# connectors.net
KiCad netlist of a schematic drawn in Altium Designer
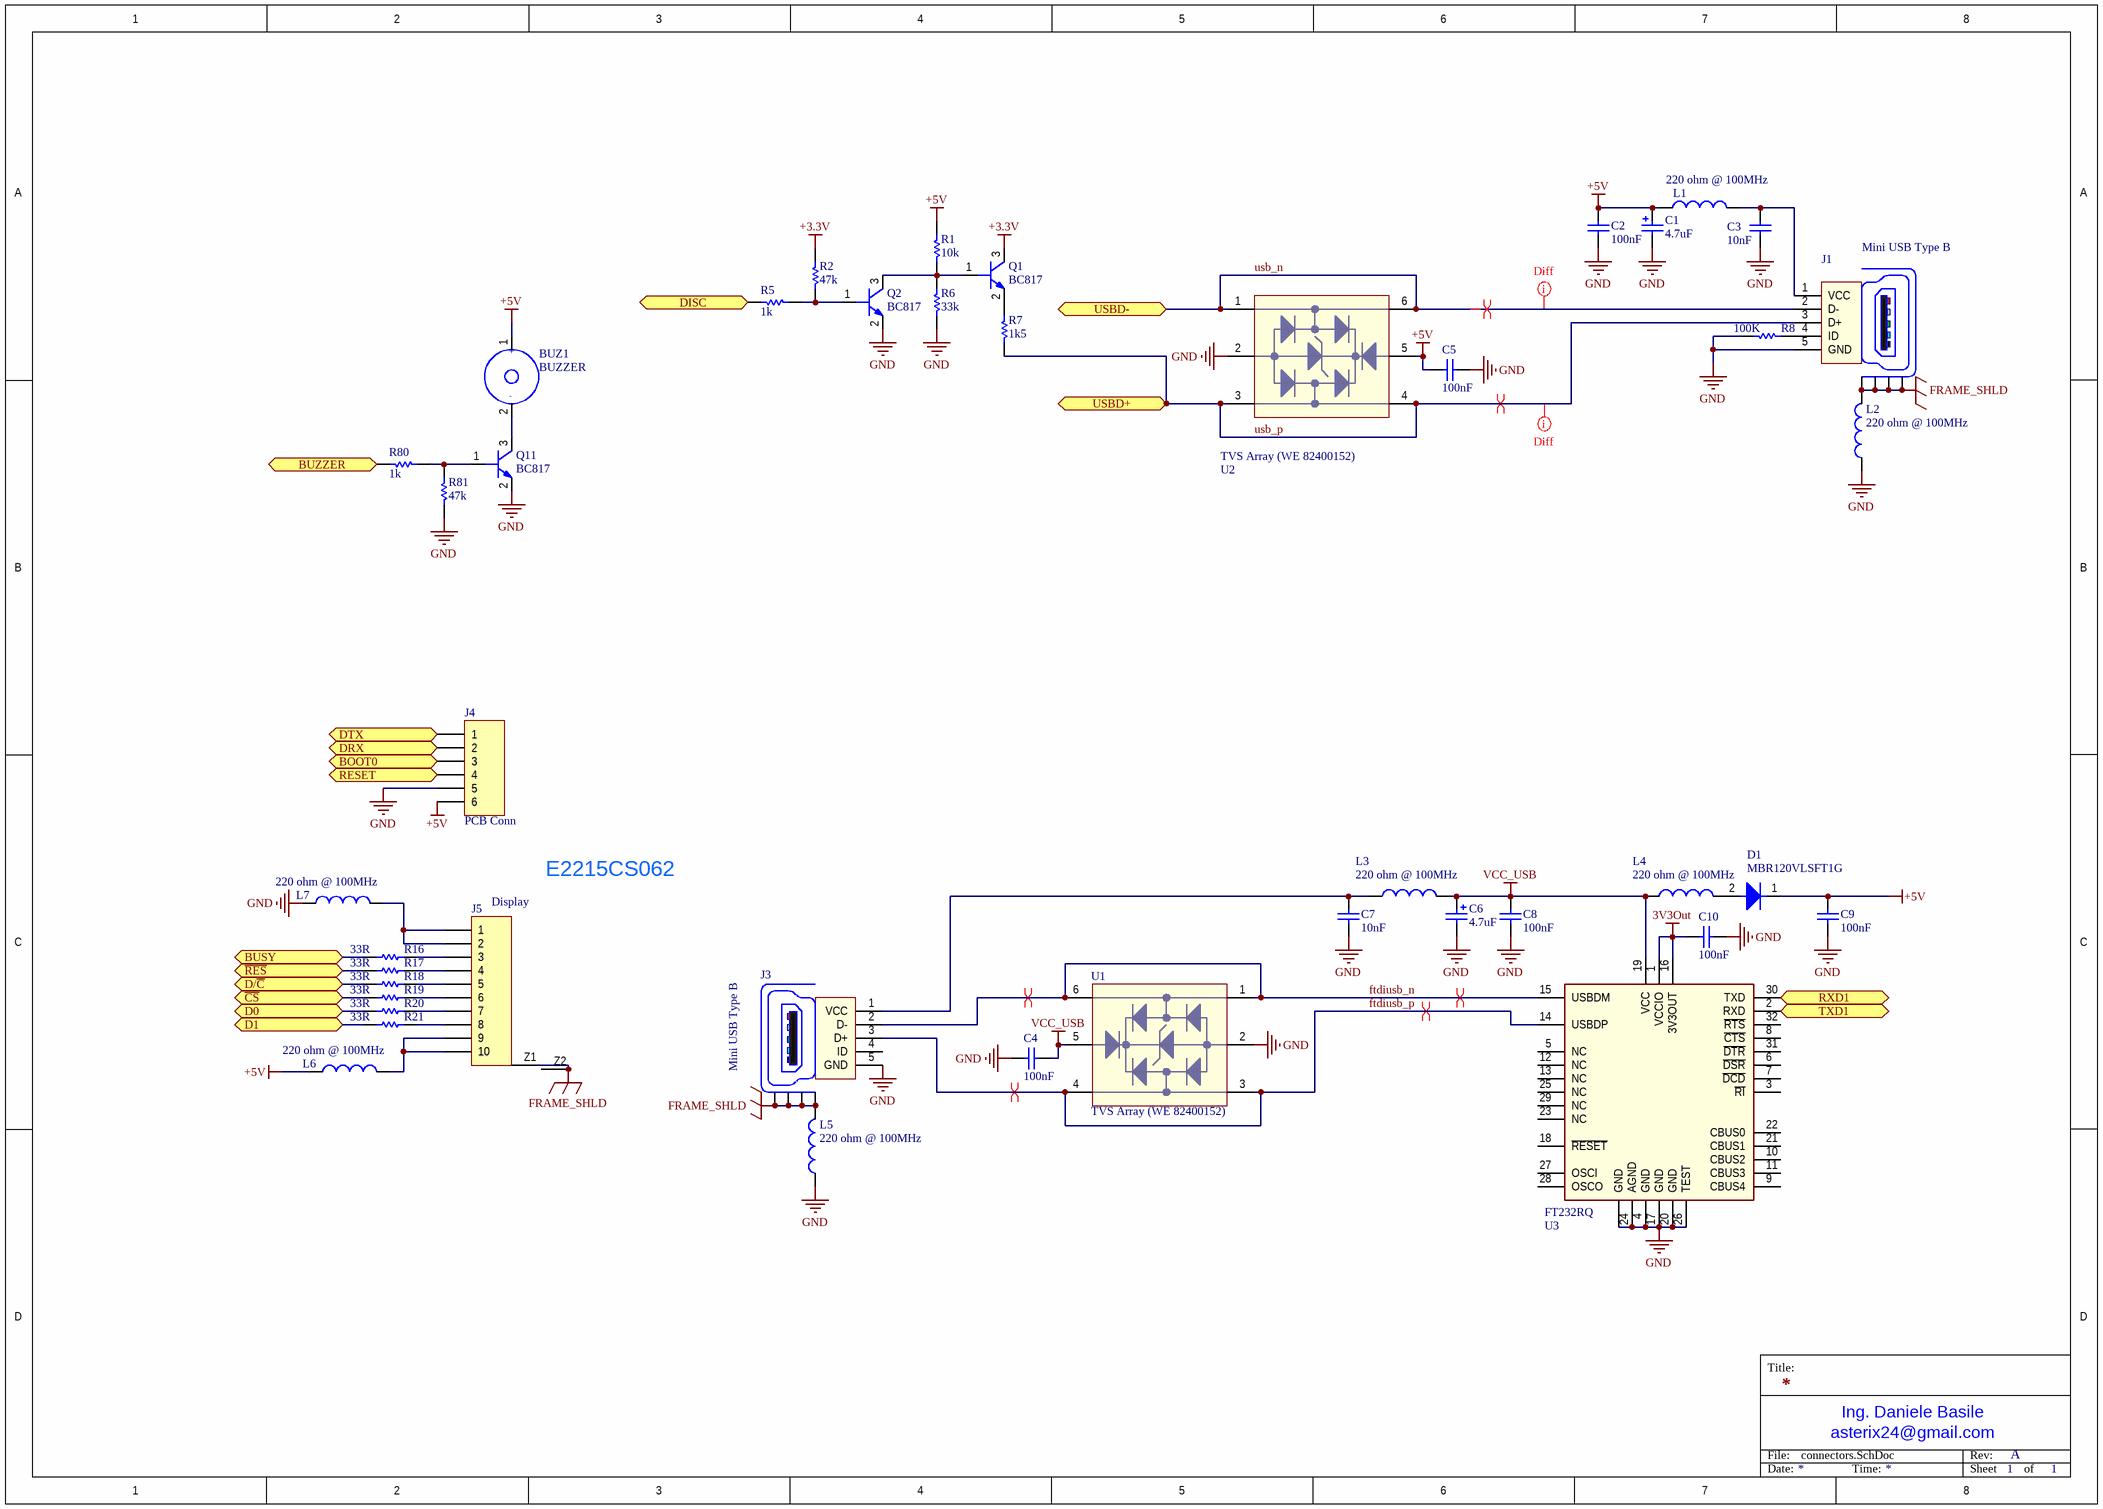
[diagram p0: connectors.SchDoc]

(export (version "E")
  (design (tool "Eeschema 10.0.6"))
  (components
    (comp (ref "BUZ1")
      (value "BUZZER")
      (footprint "buzzer_14mm_thd")
      (libsource (lib "develer_library") (part "BUZZER"))
    )
    (comp (ref "C1")
      (value "4.7uF")
      (footprint "1206_[3216]")
      (description "Ceramic X7R 16V")
      (fields (field (name "PUBLISHER") "Altium Limited"))
      (libsource (lib "DEVELER_Library") (part "Cap Pol1"))
    )
    (comp (ref "C2")
      (value "100nF")
      (footprint "0603_[1608]")
      (description "Ceramic X7R 50V")
      (fields (field (name "PUBLISHER") "Altium Limited"))
      (libsource (lib "DEVELER_Library") (part "Cap"))
    )
    (comp (ref "C3")
      (value "10nF")
      (footprint "0603_[1608]")
      (description "Ceramic X7R 50V")
      (fields (field (name "PUBLISHER") "Altium Limited"))
      (libsource (lib "DEVELER_Library") (part "Cap"))
    )
    (comp (ref "C4")
      (value "100nF")
      (footprint "0603_[1608]")
      (description "Ceramic X7R 50V")
      (fields (field (name "PUBLISHER") "Altium Limited"))
      (libsource (lib "Miscellaneous Devices") (part "Cap"))
    )
    (comp (ref "C5")
      (value "100nF")
      (footprint "0603_[1608]")
      (description "Ceramic X7R 50V")
      (fields (field (name "PUBLISHER") "Altium Limited"))
      (libsource (lib "Miscellaneous Devices") (part "Cap"))
    )
    (comp (ref "C6")
      (value "4.7uF")
      (footprint "1206_[3216]")
      (description "Ceramic X5R 25V")
      (fields (field (name "PUBLISHER") "Altium Limited"))
      (libsource (lib "DEVELER_Library") (part "Cap Pol1"))
    )
    (comp (ref "C7")
      (value "10nF")
      (footprint "0603_[1608]")
      (description "Ceramic X7R 50V")
      (fields (field (name "PUBLISHER") "Altium Limited"))
      (libsource (lib "DEVELER_Library") (part "Cap"))
    )
    (comp (ref "C8")
      (value "100nF")
      (footprint "0603_[1608]")
      (description "Ceramic X7R 50V")
      (fields (field (name "PUBLISHER") "Altium Limited"))
      (libsource (lib "DEVELER_Library") (part "Cap"))
    )
    (comp (ref "C9")
      (value "100nF")
      (footprint "0603_[1608]")
      (description "Ceramic X7R 50V")
      (fields (field (name "PUBLISHER") "Altium Limited"))
      (libsource (lib "DEVELER_Library") (part "Cap"))
    )
    (comp (ref "C10")
      (value "100nF")
      (footprint "0603_[1608]")
      (description "Ceramic X7R 50V")
      (fields (field (name "PUBLISHER") "Altium Limited"))
      (libsource (lib "DEVELER_Library") (part "Cap"))
    )
    (comp (ref "D1")
      (value "MBR120VLSFT1G")
      (footprint "SOD-123")
      (description "Diode Schottky  low Vf, If 1A (PMEG3010ER; MBRX120LF)")
      (libsource (lib "DEVELER_Library") (part "Diode"))
    )
    (comp (ref "J1")
      (value "Mini USB Type B")
      (footprint "usb_typeB_mini_smd")
      (description "Mini USB SMT Type B 5 Contacts")
      (fields
        (field (name "MANUFACTURER") "Würth Elektronik eiSos GmbH")
        (field (name "PARTNO") "65100516121")
        (field (name "CREATED BY") "Karrer Zheng")
      )
      (libsource (lib "develer_library") (part "USB_Con_Type_B_mini_SMT"))
    )
    (comp (ref "J3")
      (value "Mini USB Type B")
      (footprint "usb_typeB_mini_smd")
      (description "Mini USB SMT Type B 5 Contacts (WE 65100516121)")
      (fields
        (field (name "MANUFACTURER") "Würth Elektronik eiSos GmbH")
        (field (name "PARTNO") "65100516121")
        (field (name "CREATED BY") "Karrer Zheng")
      )
      (libsource (lib "DEVELER_Library") (part "USB_Con_Type_B_mini_SMT"))
    )
    (comp (ref "J4")
      (value "PCB Conn")
      (footprint "HEADER_1X6_2.54MM_THD")
      (description "Pin Header, 1x6, 2.54mm.")
      (fields (field (name "PUBLISHER") "Altium Limited"))
      (libsource (lib "Miscellaneous Connectors") (part "Header 6"))
    )
    (comp (ref "J5")
      (value "Display")
      (footprint "fcc-zif_10pin_0.5mm")
      (fields (field (name "PUBLISHER") "Altium Limited"))
      (libsource (lib "Miscellaneous Connectors") (part "Header 10"))
    )
    (comp (ref "L1")
      (value "220 ohm @ 100MHz")
      (footprint "0805_[2012]")
      (description "WE 742792022")
      (libsource (lib "") (part "Inductor_1"))
    )
    (comp (ref "L2")
      (value "220 ohm @ 100MHz")
      (footprint "0805_[2012]")
      (description "WE 742792022")
      (libsource (lib "") (part "Inductor_1"))
    )
    (comp (ref "L3")
      (value "220 ohm @ 100MHz")
      (footprint "0805_[2012]")
      (description "WE 742792022")
      (libsource (lib "DEVELER_Library") (part "Inductor"))
    )
    (comp (ref "L4")
      (value "220 ohm @ 100MHz")
      (footprint "0805_[2012]")
      (description "WE 742792022")
      (libsource (lib "DEVELER_Library") (part "Inductor"))
    )
    (comp (ref "L5")
      (value "220 ohm @ 100MHz")
      (footprint "0805_[2012]")
      (description "WE 742792022")
      (libsource (lib "") (part "Inductor_1"))
    )
    (comp (ref "L6")
      (value "220 ohm @ 100MHz")
      (footprint "0805_[2012]")
      (description "WE 742792022")
      (libsource (lib "") (part "Inductor_1"))
    )
    (comp (ref "L7")
      (value "220 ohm @ 100MHz")
      (footprint "0805_[2012]")
      (description "WE 742792022")
      (libsource (lib "") (part "Inductor_1"))
    )
    (comp (ref "Q1")
      (value "BC817")
      (footprint "SOT-23")
      (description "BJT NPN")
      (libsource (lib "develer_library") (part "BC817"))
    )
    (comp (ref "Q2")
      (value "BC817")
      (footprint "SOT-23")
      (description "BJT NPN")
      (libsource (lib "develer_library") (part "BC817"))
    )
    (comp (ref "Q11")
      (value "BC817")
      (footprint "SOT-23")
      (description "BJT NPN")
      (libsource (lib "develer_library") (part "BC817"))
    )
    (comp (ref "R1")
      (value "10k")
      (footprint "0603_[1608]")
      (description "Resistor")
      (fields (field (name "PUBLISHER") "Altium Limited"))
      (libsource (lib "DEVELER_Library") (part "Res1"))
    )
    (comp (ref "R2")
      (value "47k")
      (footprint "0603_[1608]")
      (description "Resistor")
      (fields (field (name "PUBLISHER") "Altium Limited"))
      (libsource (lib "DEVELER_Library") (part "Res1"))
    )
    (comp (ref "R5")
      (value "1k")
      (footprint "0603_[1608]")
      (description "Resistor")
      (fields (field (name "PUBLISHER") "Altium Limited"))
      (libsource (lib "DEVELER_Library") (part "Res1"))
    )
    (comp (ref "R6")
      (value "33k")
      (footprint "0603_[1608]")
      (description "Resistor")
      (fields (field (name "PUBLISHER") "Altium Limited"))
      (libsource (lib "DEVELER_Library") (part "Res1"))
    )
    (comp (ref "R7")
      (value "1k5")
      (footprint "0603_[1608]")
      (description "Resistor")
      (fields (field (name "PUBLISHER") "Altium Limited"))
      (libsource (lib "DEVELER_Library") (part "Res1"))
    )
    (comp (ref "R8")
      (value "100K")
      (footprint "0603_[1608]")
      (description "Resistor")
      (libsource (lib "Miscellaneous Devices") (part "Res1"))
    )
    (comp (ref "R16")
      (value "33R")
      (footprint "0603_[1608]")
      (description "Resistor")
      (fields (field (name "PUBLISHER") "Altium Limited"))
      (libsource (lib "simboli") (part "Res1"))
    )
    (comp (ref "R17")
      (value "33R")
      (footprint "0603_[1608]")
      (description "Resistor")
      (fields (field (name "PUBLISHER") "Altium Limited"))
      (libsource (lib "simboli") (part "Res1"))
    )
    (comp (ref "R18")
      (value "33R")
      (footprint "0603_[1608]")
      (description "Resistor")
      (fields (field (name "PUBLISHER") "Altium Limited"))
      (libsource (lib "simboli") (part "Res1"))
    )
    (comp (ref "R19")
      (value "33R")
      (footprint "0603_[1608]")
      (description "Resistor")
      (fields (field (name "PUBLISHER") "Altium Limited"))
      (libsource (lib "simboli") (part "Res1"))
    )
    (comp (ref "R20")
      (value "33R")
      (footprint "0603_[1608]")
      (description "Resistor")
      (fields (field (name "PUBLISHER") "Altium Limited"))
      (libsource (lib "simboli") (part "Res1"))
    )
    (comp (ref "R21")
      (value "33R")
      (footprint "0603_[1608]")
      (description "Resistor")
      (fields (field (name "PUBLISHER") "Altium Limited"))
      (libsource (lib "simboli") (part "Res1"))
    )
    (comp (ref "R80")
      (value "1k")
      (footprint "0603_[1608]")
      (description "Resistor")
      (fields (field (name "PUBLISHER") "Altium Limited"))
      (libsource (lib "DEVELER_Library") (part "Res1"))
    )
    (comp (ref "R81")
      (value "47k")
      (footprint "0603_[1608]")
      (description "Resistor")
      (fields (field (name "PUBLISHER") "Altium Limited"))
      (libsource (lib "DEVELER_Library") (part "Res1"))
    )
    (comp (ref "U1")
      (value "TVS Array (WE 82400152)")
      (footprint "SOT-563")
      (libsource (lib "DEVELER_Library") (part "TVS_Diode_Array"))
    )
    (comp (ref "U2")
      (value "TVS Array (WE 82400152)")
      (footprint "SOT-563")
      (libsource (lib "") (part "TVS_Diode_Array_1"))
    )
    (comp (ref "U3")
      (value "FT232RQ")
      (footprint "QFN-32")
      (description "Serial TTL 232 <-> USB (QFN-32)")
      (libsource (lib "DEVELER_Library") (part "FT232RQ"))
    )
  )
  (nets
    (net (code "1") (name "+3.3V") (class "Default")
      (node (ref "Q1") (pin "3") (pinfunction "C_3") (pintype "passive"))
      (node (ref "R2") (pin "1") (pinfunction "1_1") (pintype "passive"))
    )
    (net (code "2") (name "+5V") (class "Default")
      (node (ref "BUZ1") (pin "1") (pinfunction "1_1") (pintype "bidirectional"))
      (node (ref "C1") (pin "1") (pinfunction "1_1") (pintype "passive"))
      (node (ref "C2") (pin "1") (pinfunction "1_1") (pintype "passive"))
      (node (ref "C5") (pin "2") (pinfunction "2_2") (pintype "passive"))
      (node (ref "C9") (pin "2") (pinfunction "2_2") (pintype "passive"))
      (node (ref "D1") (pin "1") (pinfunction "K_1") (pintype "passive"))
      (node (ref "J4") (pin "6") (pinfunction "6_6") (pintype "passive"))
      (node (ref "L1") (pin "1") (pinfunction "1_1") (pintype "passive"))
      (node (ref "L6") (pin "1") (pinfunction "1_1") (pintype "passive"))
      (node (ref "R1") (pin "1") (pinfunction "1_1") (pintype "passive"))
      (node (ref "U2") (pin "5") (pinfunction "5_5") (pintype "passive"))
    )
    (net (code "3") (name "/BOOT0") (class "Default")
      (node (ref "J4") (pin "3") (pinfunction "3_3") (pintype "passive"))
    )
    (net (code "4") (name "/BUSY") (class "Default")
      (node (ref "R16") (pin "2") (pinfunction "2_2") (pintype "passive"))
    )
    (net (code "5") (name "/BUZZER") (class "Default")
      (node (ref "R80") (pin "2") (pinfunction "2_2") (pintype "passive"))
    )
    (net (code "6") (name "/D0") (class "Default")
      (node (ref "R20") (pin "2") (pinfunction "2_2") (pintype "passive"))
    )
    (net (code "7") (name "/D1") (class "Default")
      (node (ref "R21") (pin "2") (pinfunction "2_2") (pintype "passive"))
    )
    (net (code "8") (name "/DISC") (class "Default")
      (node (ref "R5") (pin "2") (pinfunction "2_2") (pintype "passive"))
    )
    (net (code "9") (name "/DRX") (class "Default")
      (node (ref "J4") (pin "2") (pinfunction "2_2") (pintype "passive"))
    )
    (net (code "10") (name "/DTX") (class "Default")
      (node (ref "J4") (pin "1") (pinfunction "1_1") (pintype "passive"))
    )
    (net (code "11") (name "/D{slash}~{C}") (class "Default")
      (node (ref "R18") (pin "2") (pinfunction "2_2") (pintype "passive"))
    )
    (net (code "12") (name "/RESET") (class "Default")
      (node (ref "J4") (pin "4") (pinfunction "4_4") (pintype "passive"))
    )
    (net (code "13") (name "/RXD1") (class "Default")
      (node (ref "U3") (pin "30") (pinfunction "TXD_30") (pintype "passive"))
    )
    (net (code "14") (name "/TXD1") (class "Default")
      (node (ref "U3") (pin "2") (pinfunction "RXD_2") (pintype "passive"))
    )
    (net (code "15") (name "/ftdiusb_n") (class "Default")
      (node (ref "J3") (pin "2") (pinfunction "D-_2") (pintype "passive"))
      (node (ref "U1") (pin "1") (pinfunction "1_1") (pintype "passive"))
      (node (ref "U1") (pin "6") (pinfunction "6_6") (pintype "passive"))
      (node (ref "U3") (pin "15") (pinfunction "USBDM_15") (pintype "passive"))
    )
    (net (code "16") (name "/ftdiusb_p") (class "Default")
      (node (ref "J3") (pin "3") (pinfunction "D+_3") (pintype "passive"))
      (node (ref "U1") (pin "3") (pinfunction "3_3") (pintype "passive"))
      (node (ref "U1") (pin "4") (pinfunction "4_4") (pintype "passive"))
      (node (ref "U3") (pin "14") (pinfunction "USBDP_14") (pintype "passive"))
    )
    (net (code "17") (name "/usb_n") (class "Default")
      (node (ref "J1") (pin "2") (pinfunction "D-_2") (pintype "passive"))
      (node (ref "U2") (pin "1") (pinfunction "1_1") (pintype "passive"))
      (node (ref "U2") (pin "6") (pinfunction "6_6") (pintype "passive"))
    )
    (net (code "18") (name "/usb_p") (class "Default")
      (node (ref "J1") (pin "3") (pinfunction "D+_3") (pintype "passive"))
      (node (ref "R7") (pin "2") (pinfunction "2_2") (pintype "passive"))
      (node (ref "U2") (pin "3") (pinfunction "3_3") (pintype "passive"))
      (node (ref "U2") (pin "4") (pinfunction "4_4") (pintype "passive"))
    )
    (net (code "19") (name "/~{CS}") (class "Default")
      (node (ref "R19") (pin "2") (pinfunction "2_2") (pintype "passive"))
    )
    (net (code "20") (name "/~{RES}") (class "Default")
      (node (ref "R17") (pin "2") (pinfunction "2_2") (pintype "passive"))
    )
    (net (code "21") (name "3V3Out") (class "Default")
      (node (ref "C10") (pin "1") (pinfunction "1_1") (pintype "passive"))
      (node (ref "U3") (pin "1") (pinfunction "VCCIO_1") (pintype "passive"))
      (node (ref "U3") (pin "16") (pinfunction "3V3OUT_16") (pintype "passive"))
    )
    (net (code "22") (name "FRAME_SHLD") (class "Default")
      (node (ref "J1") (pin "Z1") (pinfunction "Shield_Z1") (pintype "passive"))
      (node (ref "J1") (pin "Z2") (pinfunction "Shield_Z2") (pintype "passive"))
      (node (ref "J1") (pin "Z3") (pinfunction "Shield_Z3") (pintype "passive"))
      (node (ref "J1") (pin "Z4") (pinfunction "Shield_Z4") (pintype "passive"))
      (node (ref "J3") (pin "Z1") (pinfunction "Shield_Z1") (pintype "passive"))
      (node (ref "J3") (pin "Z2") (pinfunction "Shield_Z2") (pintype "passive"))
      (node (ref "J3") (pin "Z3") (pinfunction "Shield_Z3") (pintype "passive"))
      (node (ref "J3") (pin "Z4") (pinfunction "Shield_Z4") (pintype "passive"))
      (node (ref "J5") (pin "Z1") (pinfunction "Z1_Z1") (pintype "passive"))
      (node (ref "J5") (pin "Z2") (pinfunction "Z2_Z2") (pintype "passive"))
      (node (ref "L2") (pin "2") (pinfunction "2_2") (pintype "passive"))
      (node (ref "L5") (pin "2") (pinfunction "2_2") (pintype "passive"))
    )
    (net (code "23") (name "GND") (class "Default")
      (node (ref "C1") (pin "2") (pinfunction "2_2") (pintype "passive"))
      (node (ref "C10") (pin "2") (pinfunction "2_2") (pintype "passive"))
      (node (ref "C2") (pin "2") (pinfunction "2_2") (pintype "passive"))
      (node (ref "C3") (pin "2") (pinfunction "2_2") (pintype "passive"))
      (node (ref "C4") (pin "1") (pinfunction "1_1") (pintype "passive"))
      (node (ref "C5") (pin "1") (pinfunction "1_1") (pintype "passive"))
      (node (ref "C6") (pin "2") (pinfunction "2_2") (pintype "passive"))
      (node (ref "C7") (pin "2") (pinfunction "2_2") (pintype "passive"))
      (node (ref "C8") (pin "2") (pinfunction "2_2") (pintype "passive"))
      (node (ref "C9") (pin "1") (pinfunction "1_1") (pintype "passive"))
      (node (ref "J1") (pin "5") (pinfunction "GND_5") (pintype "passive"))
      (node (ref "J3") (pin "5") (pinfunction "GND_5") (pintype "passive"))
      (node (ref "J4") (pin "5") (pinfunction "5_5") (pintype "passive"))
      (node (ref "L2") (pin "1") (pinfunction "1_1") (pintype "passive"))
      (node (ref "L5") (pin "1") (pinfunction "1_1") (pintype "passive"))
      (node (ref "L7") (pin "1") (pinfunction "1_1") (pintype "passive"))
      (node (ref "Q11") (pin "2") (pinfunction "E_2") (pintype "passive"))
      (node (ref "Q2") (pin "2") (pinfunction "E_2") (pintype "passive"))
      (node (ref "R6") (pin "2") (pinfunction "2_2") (pintype "passive"))
      (node (ref "R8") (pin "2") (pinfunction "2_2") (pintype "passive"))
      (node (ref "R81") (pin "2") (pinfunction "2_2") (pintype "passive"))
      (node (ref "U1") (pin "2") (pinfunction "2_2") (pintype "passive"))
      (node (ref "U2") (pin "2") (pinfunction "2_2") (pintype "passive"))
      (node (ref "U3") (pin "17") (pinfunction "GND_17") (pintype "passive"))
      (node (ref "U3") (pin "20") (pinfunction "GND_20") (pintype "passive"))
      (node (ref "U3") (pin "24") (pinfunction "AGND_24") (pintype "passive"))
      (node (ref "U3") (pin "26") (pinfunction "TEST_26") (pintype "passive"))
      (node (ref "U3") (pin "4") (pinfunction "GND_4") (pintype "passive"))
      (node (ref "U3") (pin "GND_PAD") (pinfunction "GND_GND_PAD") (pintype "passive"))
    )
    (net (code "24") (name "Net-(D1-A)") (class "Default")
      (node (ref "D1") (pin "2") (pinfunction "A_2") (pintype "passive"))
      (node (ref "L4") (pin "1") (pinfunction "1_1") (pintype "passive"))
    )
    (net (code "25") (name "Net-(J1-ID)") (class "Default")
      (node (ref "J1") (pin "4") (pinfunction "ID_4") (pintype "passive"))
      (node (ref "R8") (pin "1") (pinfunction "1_1") (pintype "passive"))
    )
    (net (code "26") (name "Net-(J1-VCC)") (class "Default")
      (node (ref "C3") (pin "1") (pinfunction "1_1") (pintype "passive"))
      (node (ref "J1") (pin "1") (pinfunction "VCC_1") (pintype "passive"))
      (node (ref "L1") (pin "2") (pinfunction "2_2") (pintype "passive"))
    )
    (net (code "27") (name "Net-(J3-VCC)") (class "Default")
      (node (ref "C7") (pin "1") (pinfunction "1_1") (pintype "passive"))
      (node (ref "J3") (pin "1") (pinfunction "VCC_1") (pintype "passive"))
      (node (ref "L3") (pin "2") (pinfunction "2_2") (pintype "passive"))
    )
    (net (code "28") (name "Net-(J5-Pad1)") (class "Default")
      (node (ref "J5") (pin "1") (pinfunction "1_1") (pintype "passive"))
      (node (ref "J5") (pin "2") (pinfunction "2_2") (pintype "passive"))
      (node (ref "L7") (pin "2") (pinfunction "2_2") (pintype "passive"))
    )
    (net (code "29") (name "Net-(J5-Pad3)") (class "Default")
      (node (ref "J5") (pin "3") (pinfunction "3_3") (pintype "passive"))
      (node (ref "R16") (pin "1") (pinfunction "1_1") (pintype "passive"))
    )
    (net (code "30") (name "Net-(J5-Pad4)") (class "Default")
      (node (ref "J5") (pin "4") (pinfunction "4_4") (pintype "passive"))
      (node (ref "R17") (pin "1") (pinfunction "1_1") (pintype "passive"))
    )
    (net (code "31") (name "Net-(J5-Pad5)") (class "Default")
      (node (ref "J5") (pin "5") (pinfunction "5_5") (pintype "passive"))
      (node (ref "R18") (pin "1") (pinfunction "1_1") (pintype "passive"))
    )
    (net (code "32") (name "Net-(J5-Pad6)") (class "Default")
      (node (ref "J5") (pin "6") (pinfunction "6_6") (pintype "passive"))
      (node (ref "R19") (pin "1") (pinfunction "1_1") (pintype "passive"))
    )
    (net (code "33") (name "Net-(J5-Pad7)") (class "Default")
      (node (ref "J5") (pin "7") (pinfunction "7_7") (pintype "passive"))
      (node (ref "R20") (pin "1") (pinfunction "1_1") (pintype "passive"))
    )
    (net (code "34") (name "Net-(J5-Pad8)") (class "Default")
      (node (ref "J5") (pin "8") (pinfunction "8_8") (pintype "passive"))
      (node (ref "R21") (pin "1") (pinfunction "1_1") (pintype "passive"))
    )
    (net (code "35") (name "Net-(J5-Pad10)") (class "Default")
      (node (ref "J5") (pin "10") (pinfunction "10_10") (pintype "passive"))
      (node (ref "J5") (pin "9") (pinfunction "9_9") (pintype "passive"))
      (node (ref "L6") (pin "2") (pinfunction "2_2") (pintype "passive"))
    )
    (net (code "36") (name "Net-(Q1-B)") (class "Default")
      (node (ref "Q1") (pin "1") (pinfunction "B_1") (pintype "passive"))
      (node (ref "Q2") (pin "3") (pinfunction "C_3") (pintype "passive"))
      (node (ref "R1") (pin "2") (pinfunction "2_2") (pintype "passive"))
      (node (ref "R6") (pin "1") (pinfunction "1_1") (pintype "passive"))
    )
    (net (code "37") (name "Net-(Q1-E)") (class "Default")
      (node (ref "Q1") (pin "2") (pinfunction "E_2") (pintype "passive"))
      (node (ref "R7") (pin "1") (pinfunction "1_1") (pintype "passive"))
    )
    (net (code "38") (name "Net-(Q2-B)") (class "Default")
      (node (ref "Q2") (pin "1") (pinfunction "B_1") (pintype "passive"))
      (node (ref "R2") (pin "2") (pinfunction "2_2") (pintype "passive"))
      (node (ref "R5") (pin "1") (pinfunction "1_1") (pintype "passive"))
    )
    (net (code "39") (name "Net-(Q11-B)") (class "Default")
      (node (ref "Q11") (pin "1") (pinfunction "B_1") (pintype "passive"))
      (node (ref "R80") (pin "1") (pinfunction "1_1") (pintype "passive"))
      (node (ref "R81") (pin "1") (pinfunction "1_1") (pintype "passive"))
    )
    (net (code "40") (name "Net-(Q11-C)") (class "Default")
      (node (ref "BUZ1") (pin "2") (pinfunction "2_2") (pintype "bidirectional"))
      (node (ref "Q11") (pin "3") (pinfunction "C_3") (pintype "passive"))
    )
    (net (code "41") (name "VCC_USB") (class "Default")
      (node (ref "C4") (pin "2") (pinfunction "2_2") (pintype "passive"))
      (node (ref "C6") (pin "1") (pinfunction "1_1") (pintype "passive"))
      (node (ref "C8") (pin "1") (pinfunction "1_1") (pintype "passive"))
      (node (ref "L3") (pin "1") (pinfunction "1_1") (pintype "passive"))
      (node (ref "L4") (pin "2") (pinfunction "2_2") (pintype "passive"))
      (node (ref "U1") (pin "5") (pinfunction "5_5") (pintype "passive"))
      (node (ref "U3") (pin "19") (pinfunction "VCC_19") (pintype "passive"))
    )
    (net (code "42") (name "unconnected-(J3-ID-Pad4)") (class "Default")
      (node (ref "J3") (pin "4") (pinfunction "ID_4") (pintype "passive"))
    )
    (net (code "43") (name "unconnected-(U3-CBUS0-Pad22)") (class "Default")
      (node (ref "U3") (pin "22") (pinfunction "CBUS0_22") (pintype "passive"))
    )
    (net (code "44") (name "unconnected-(U3-CBUS1-Pad21)") (class "Default")
      (node (ref "U3") (pin "21") (pinfunction "CBUS1_21") (pintype "passive"))
    )
    (net (code "45") (name "unconnected-(U3-CBUS2-Pad10)") (class "Default")
      (node (ref "U3") (pin "10") (pinfunction "CBUS2_10") (pintype "passive"))
    )
    (net (code "46") (name "unconnected-(U3-CBUS3-Pad11)") (class "Default")
      (node (ref "U3") (pin "11") (pinfunction "CBUS3_11") (pintype "passive"))
    )
    (net (code "47") (name "unconnected-(U3-CBUS4-Pad9)") (class "Default")
      (node (ref "U3") (pin "9") (pinfunction "CBUS4_9") (pintype "passive"))
    )
    (net (code "48") (name "unconnected-(U3-NC-Pad5)") (class "Default")
      (node (ref "U3") (pin "5") (pinfunction "NC_5") (pintype "passive"))
    )
    (net (code "49") (name "unconnected-(U3-NC-Pad12)") (class "Default")
      (node (ref "U3") (pin "12") (pinfunction "NC_12") (pintype "passive"))
    )
    (net (code "50") (name "unconnected-(U3-NC-Pad13)") (class "Default")
      (node (ref "U3") (pin "13") (pinfunction "NC_13") (pintype "passive"))
    )
    (net (code "51") (name "unconnected-(U3-NC-Pad23)") (class "Default")
      (node (ref "U3") (pin "23") (pinfunction "NC_23") (pintype "passive"))
    )
    (net (code "52") (name "unconnected-(U3-NC-Pad25)") (class "Default")
      (node (ref "U3") (pin "25") (pinfunction "NC_25") (pintype "passive"))
    )
    (net (code "53") (name "unconnected-(U3-NC-Pad29)") (class "Default")
      (node (ref "U3") (pin "29") (pinfunction "NC_29") (pintype "passive"))
    )
    (net (code "54") (name "unconnected-(U3-OSCI-Pad27)") (class "Default")
      (node (ref "U3") (pin "27") (pinfunction "OSCI_27") (pintype "passive"))
    )
    (net (code "55") (name "unconnected-(U3-OSCO-Pad28)") (class "Default")
      (node (ref "U3") (pin "28") (pinfunction "OSCO_28") (pintype "passive"))
    )
    (net (code "56") (name "unconnected-(U3-~{CTS}-Pad8)") (class "Default")
      (node (ref "U3") (pin "8") (pinfunction "~{CTS}_8") (pintype "passive"))
    )
    (net (code "57") (name "unconnected-(U3-~{DCD}-Pad7)") (class "Default")
      (node (ref "U3") (pin "7") (pinfunction "~{DCD}_7") (pintype "passive"))
    )
    (net (code "58") (name "unconnected-(U3-~{DSR}-Pad6)") (class "Default")
      (node (ref "U3") (pin "6") (pinfunction "~{DSR}_6") (pintype "passive"))
    )
    (net (code "59") (name "unconnected-(U3-~{DTR}-Pad31)") (class "Default")
      (node (ref "U3") (pin "31") (pinfunction "~{DTR}_31") (pintype "passive"))
    )
    (net (code "60") (name "unconnected-(U3-~{RESET}-Pad18)") (class "Default")
      (node (ref "U3") (pin "18") (pinfunction "~{RESET}_18") (pintype "passive"))
    )
    (net (code "61") (name "unconnected-(U3-~{RI}-Pad3)") (class "Default")
      (node (ref "U3") (pin "3") (pinfunction "~{RI}_3") (pintype "passive"))
    )
    (net (code "62") (name "unconnected-(U3-~{RTS}-Pad32)") (class "Default")
      (node (ref "U3") (pin "32") (pinfunction "~{RTS}_32") (pintype "passive"))
    )
  )
)
